# ampli.net
KiCad netlist of a schematic drawn in EAGLE
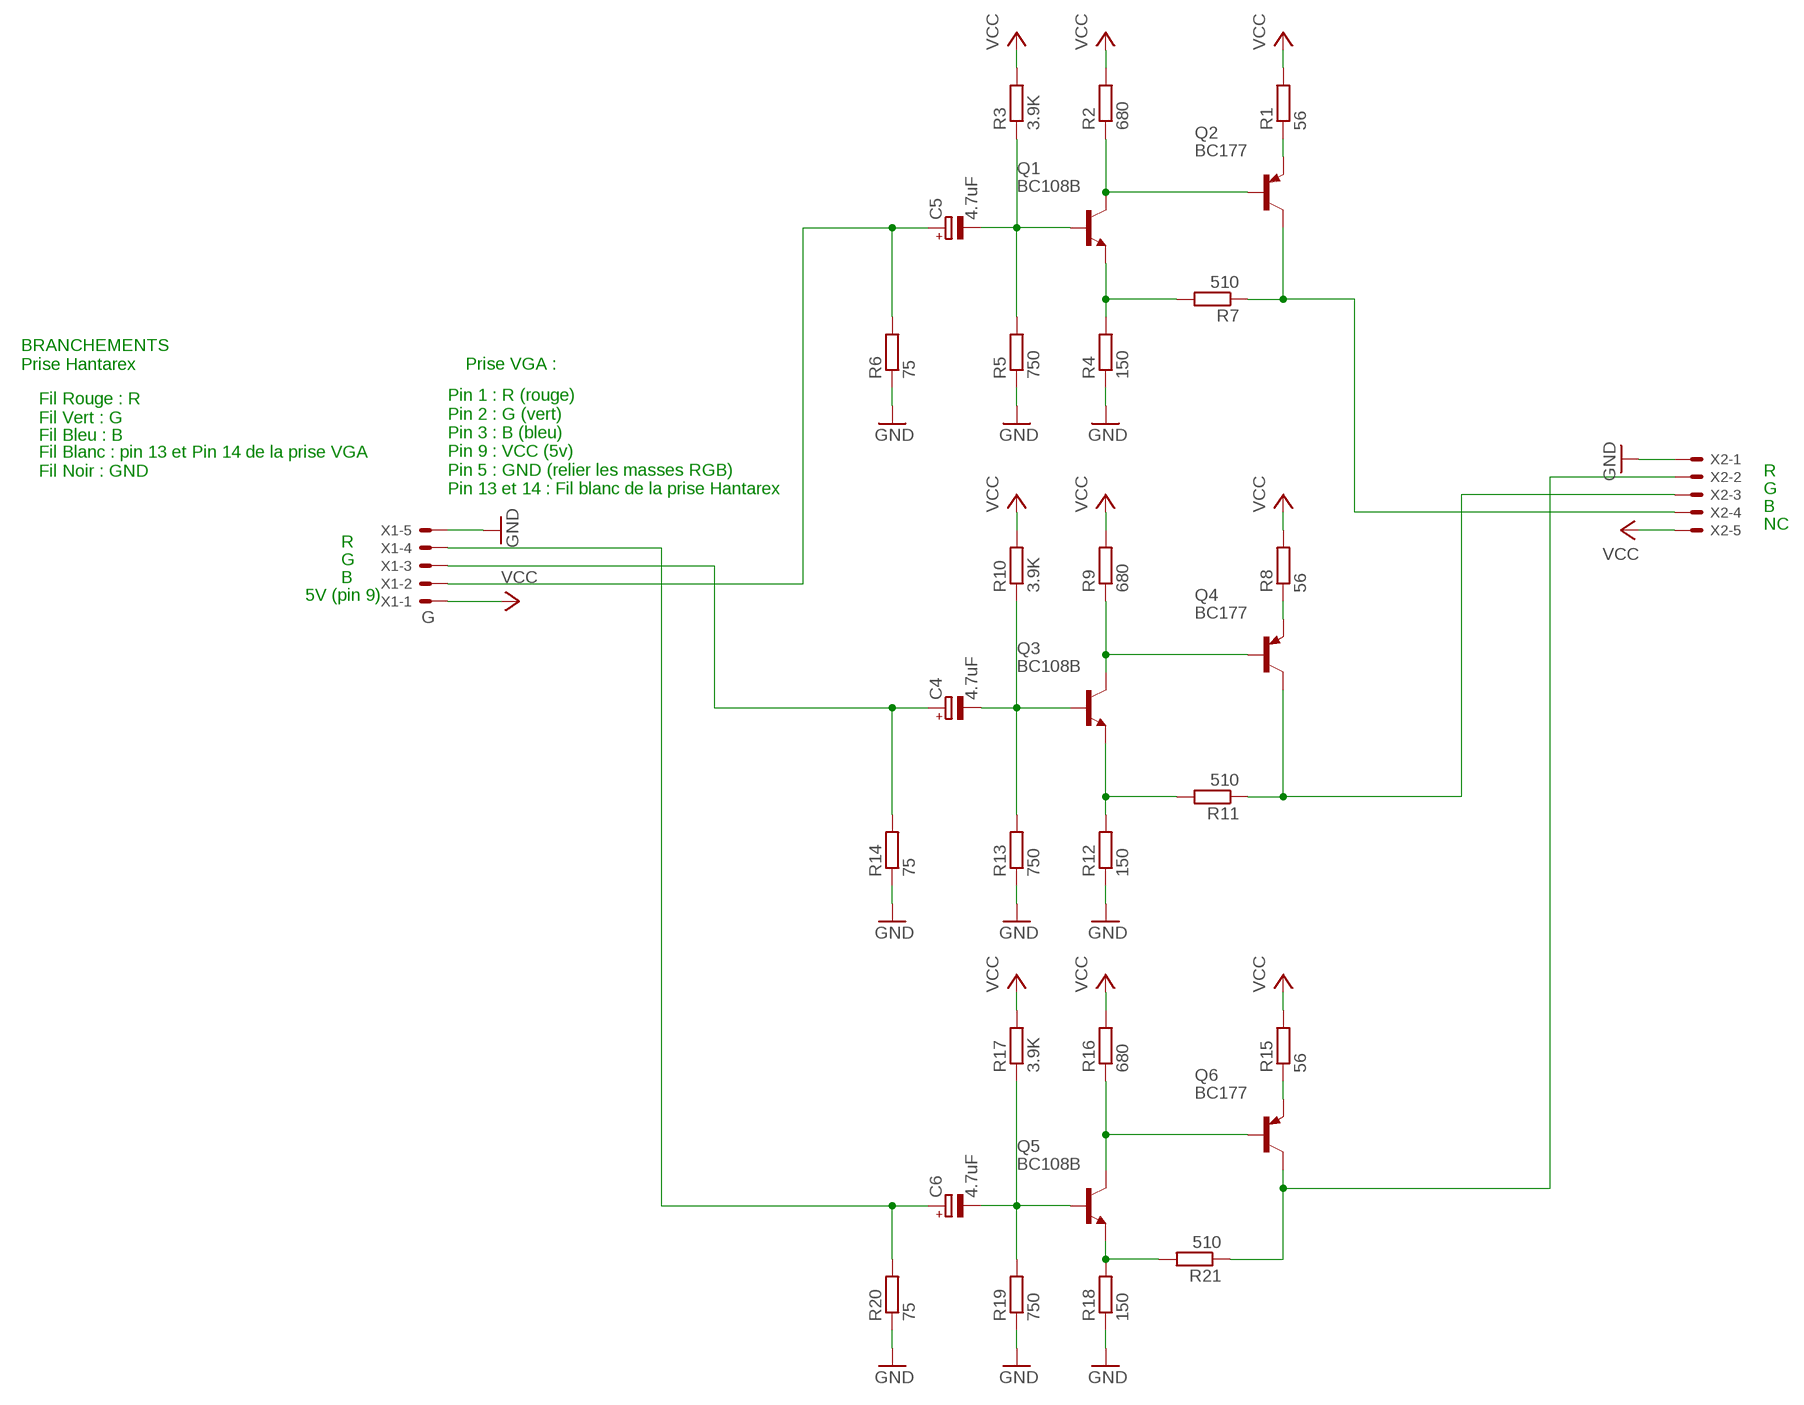
[diagram p0: schematic, sheet 1]

(export (version "E")
  (design (tool "Eeschema 10.0.6"))
  (components
    (comp (ref "C4")
      (value "4.7uF")
      (footprint "eagle-import:E5-10,5")
      (libsource (lib "eagle-import") (part "CPOL-EUE5-10.5"))
    )
    (comp (ref "C5")
      (value "4.7uF")
      (footprint "eagle-import:E5-10,5")
      (libsource (lib "eagle-import") (part "CPOL-EUE5-10.5"))
    )
    (comp (ref "C6")
      (value "4.7uF")
      (footprint "eagle-import:E5-10,5")
      (libsource (lib "eagle-import") (part "CPOL-EUE5-10.5"))
    )
    (comp (ref "Q1")
      (value "BC108B")
      (footprint "eagle-import:TO18")
      (libsource (lib "eagle-import") (part "BC108B"))
    )
    (comp (ref "Q2")
      (value "BC177")
      (footprint "eagle-import:TO18")
      (libsource (lib "eagle-import") (part "BC177"))
    )
    (comp (ref "Q3")
      (value "BC108B")
      (footprint "eagle-import:TO18")
      (libsource (lib "eagle-import") (part "BC108B"))
    )
    (comp (ref "Q4")
      (value "BC177")
      (footprint "eagle-import:TO18")
      (libsource (lib "eagle-import") (part "BC177"))
    )
    (comp (ref "Q5")
      (value "BC108B")
      (footprint "eagle-import:TO18")
      (libsource (lib "eagle-import") (part "BC108B"))
    )
    (comp (ref "Q6")
      (value "BC177")
      (footprint "eagle-import:TO18")
      (libsource (lib "eagle-import") (part "BC177"))
    )
    (comp (ref "R1")
      (value "56")
      (footprint "eagle-import:0207_10")
      (libsource (lib "eagle-import") (part "R-EU_0207/10"))
    )
    (comp (ref "R2")
      (value "680")
      (footprint "eagle-import:0207_10")
      (libsource (lib "eagle-import") (part "R-EU_0207/10"))
    )
    (comp (ref "R3")
      (value "3.9K")
      (footprint "eagle-import:0207_10")
      (libsource (lib "eagle-import") (part "R-EU_0207/10"))
    )
    (comp (ref "R4")
      (value "150")
      (footprint "eagle-import:0207_10")
      (libsource (lib "eagle-import") (part "R-EU_0207/10"))
    )
    (comp (ref "R5")
      (value "750")
      (footprint "eagle-import:0207_10")
      (libsource (lib "eagle-import") (part "R-EU_0207/10"))
    )
    (comp (ref "R6")
      (value "75")
      (footprint "eagle-import:0207_10")
      (libsource (lib "eagle-import") (part "R-EU_0207/10"))
    )
    (comp (ref "R7")
      (value "510")
      (footprint "eagle-import:0207_10")
      (libsource (lib "eagle-import") (part "R-EU_0207/10"))
    )
    (comp (ref "R8")
      (value "56")
      (footprint "eagle-import:0207_10")
      (libsource (lib "eagle-import") (part "R-EU_0207/10"))
    )
    (comp (ref "R9")
      (value "680")
      (footprint "eagle-import:0207_10")
      (libsource (lib "eagle-import") (part "R-EU_0207/10"))
    )
    (comp (ref "R10")
      (value "3.9K")
      (footprint "eagle-import:0207_10")
      (libsource (lib "eagle-import") (part "R-EU_0207/10"))
    )
    (comp (ref "R11")
      (value "510")
      (footprint "eagle-import:0207_10")
      (libsource (lib "eagle-import") (part "R-EU_0207/10"))
    )
    (comp (ref "R12")
      (value "150")
      (footprint "eagle-import:0207_10")
      (libsource (lib "eagle-import") (part "R-EU_0207/10"))
    )
    (comp (ref "R13")
      (value "750")
      (footprint "eagle-import:0207_10")
      (libsource (lib "eagle-import") (part "R-EU_0207/10"))
    )
    (comp (ref "R14")
      (value "75")
      (footprint "eagle-import:0207_10")
      (libsource (lib "eagle-import") (part "R-EU_0207/10"))
    )
    (comp (ref "R15")
      (value "56")
      (footprint "eagle-import:0207_10")
      (libsource (lib "eagle-import") (part "R-EU_0207/10"))
    )
    (comp (ref "R16")
      (value "680")
      (footprint "eagle-import:0207_10")
      (libsource (lib "eagle-import") (part "R-EU_0207/10"))
    )
    (comp (ref "R17")
      (value "3.9K")
      (footprint "eagle-import:0207_10")
      (libsource (lib "eagle-import") (part "R-EU_0207/10"))
    )
    (comp (ref "R18")
      (value "150")
      (footprint "eagle-import:0207_10")
      (libsource (lib "eagle-import") (part "R-EU_0207/10"))
    )
    (comp (ref "R19")
      (value "750")
      (footprint "eagle-import:0207_10")
      (libsource (lib "eagle-import") (part "R-EU_0207/10"))
    )
    (comp (ref "R20")
      (value "75")
      (footprint "eagle-import:0207_10")
      (libsource (lib "eagle-import") (part "R-EU_0207/10"))
    )
    (comp (ref "R21")
      (value "510")
      (footprint "eagle-import:0207_10")
      (libsource (lib "eagle-import") (part "R-EU_0207/10"))
    )
    (comp (ref "X1")
      (value "G")
      (footprint "eagle-import:KK-156-5")
      (libsource (lib "eagle-import") (part "KK-156-5"))
    )
    (comp (ref "X2")
      (value "KK-156-5")
      (footprint "eagle-import:KK-156-5")
      (libsource (lib "eagle-import") (part "KK-156-5"))
    )
  )
  (nets
    (net (code "1") (name "GND") (class "Default")
      (node (ref "R12") (pin "1") (pinfunction "1_1") (pintype "passive"))
      (node (ref "R13") (pin "1") (pinfunction "1_1") (pintype "passive"))
      (node (ref "R14") (pin "1") (pinfunction "1_1") (pintype "passive"))
      (node (ref "R18") (pin "1") (pinfunction "1_1") (pintype "passive"))
      (node (ref "R19") (pin "1") (pinfunction "1_1") (pintype "passive"))
      (node (ref "R20") (pin "1") (pinfunction "1_1") (pintype "passive"))
      (node (ref "R4") (pin "1") (pinfunction "1_1") (pintype "passive"))
      (node (ref "R5") (pin "1") (pinfunction "1_1") (pintype "passive"))
      (node (ref "R6") (pin "1") (pinfunction "1_1") (pintype "passive"))
      (node (ref "X1") (pin "5") (pinfunction "S_5") (pintype "passive"))
      (node (ref "X2") (pin "1") (pinfunction "S_1") (pintype "passive"))
    )
    (net (code "2") (name "Net-(Q1-B)") (class "Default")
      (node (ref "C5") (pin "-") (pinfunction "-_-") (pintype "passive"))
      (node (ref "Q1") (pin "2") (pinfunction "B_2") (pintype "passive"))
      (node (ref "R3") (pin "1") (pinfunction "1_1") (pintype "passive"))
      (node (ref "R5") (pin "2") (pinfunction "2_2") (pintype "passive"))
    )
    (net (code "3") (name "Net-(Q1-C)") (class "Default")
      (node (ref "Q1") (pin "3") (pinfunction "C_3") (pintype "passive"))
      (node (ref "Q2") (pin "2") (pinfunction "B_2") (pintype "passive"))
      (node (ref "R2") (pin "1") (pinfunction "1_1") (pintype "passive"))
    )
    (net (code "4") (name "Net-(Q1-E)") (class "Default")
      (node (ref "Q1") (pin "1") (pinfunction "E_1") (pintype "passive"))
      (node (ref "R4") (pin "2") (pinfunction "2_2") (pintype "passive"))
      (node (ref "R7") (pin "2") (pinfunction "2_2") (pintype "passive"))
    )
    (net (code "5") (name "Net-(Q2-C)") (class "Default")
      (node (ref "Q2") (pin "3") (pinfunction "C_3") (pintype "passive"))
      (node (ref "R7") (pin "1") (pinfunction "1_1") (pintype "passive"))
      (node (ref "X2") (pin "4") (pinfunction "S_4") (pintype "passive"))
    )
    (net (code "6") (name "Net-(Q2-E)") (class "Default")
      (node (ref "Q2") (pin "1") (pinfunction "E_1") (pintype "passive"))
      (node (ref "R1") (pin "1") (pinfunction "1_1") (pintype "passive"))
    )
    (net (code "7") (name "Net-(Q3-B)") (class "Default")
      (node (ref "C4") (pin "-") (pinfunction "-_-") (pintype "passive"))
      (node (ref "Q3") (pin "2") (pinfunction "B_2") (pintype "passive"))
      (node (ref "R10") (pin "1") (pinfunction "1_1") (pintype "passive"))
      (node (ref "R13") (pin "2") (pinfunction "2_2") (pintype "passive"))
    )
    (net (code "8") (name "Net-(Q3-C)") (class "Default")
      (node (ref "Q3") (pin "3") (pinfunction "C_3") (pintype "passive"))
      (node (ref "Q4") (pin "2") (pinfunction "B_2") (pintype "passive"))
      (node (ref "R9") (pin "1") (pinfunction "1_1") (pintype "passive"))
    )
    (net (code "9") (name "Net-(Q3-E)") (class "Default")
      (node (ref "Q3") (pin "1") (pinfunction "E_1") (pintype "passive"))
      (node (ref "R11") (pin "2") (pinfunction "2_2") (pintype "passive"))
      (node (ref "R12") (pin "2") (pinfunction "2_2") (pintype "passive"))
    )
    (net (code "10") (name "Net-(Q4-C)") (class "Default")
      (node (ref "Q4") (pin "3") (pinfunction "C_3") (pintype "passive"))
      (node (ref "R11") (pin "1") (pinfunction "1_1") (pintype "passive"))
      (node (ref "X2") (pin "3") (pinfunction "S_3") (pintype "passive"))
    )
    (net (code "11") (name "Net-(Q4-E)") (class "Default")
      (node (ref "Q4") (pin "1") (pinfunction "E_1") (pintype "passive"))
      (node (ref "R8") (pin "1") (pinfunction "1_1") (pintype "passive"))
    )
    (net (code "12") (name "Net-(Q5-B)") (class "Default")
      (node (ref "C6") (pin "-") (pinfunction "-_-") (pintype "passive"))
      (node (ref "Q5") (pin "2") (pinfunction "B_2") (pintype "passive"))
      (node (ref "R17") (pin "1") (pinfunction "1_1") (pintype "passive"))
      (node (ref "R19") (pin "2") (pinfunction "2_2") (pintype "passive"))
    )
    (net (code "13") (name "Net-(Q5-C)") (class "Default")
      (node (ref "Q5") (pin "3") (pinfunction "C_3") (pintype "passive"))
      (node (ref "Q6") (pin "2") (pinfunction "B_2") (pintype "passive"))
      (node (ref "R16") (pin "1") (pinfunction "1_1") (pintype "passive"))
    )
    (net (code "14") (name "Net-(Q5-E)") (class "Default")
      (node (ref "Q5") (pin "1") (pinfunction "E_1") (pintype "passive"))
      (node (ref "R18") (pin "2") (pinfunction "2_2") (pintype "passive"))
      (node (ref "R21") (pin "2") (pinfunction "2_2") (pintype "passive"))
    )
    (net (code "15") (name "Net-(Q6-C)") (class "Default")
      (node (ref "Q6") (pin "3") (pinfunction "C_3") (pintype "passive"))
      (node (ref "R21") (pin "1") (pinfunction "1_1") (pintype "passive"))
      (node (ref "X2") (pin "2") (pinfunction "S_2") (pintype "passive"))
    )
    (net (code "16") (name "Net-(Q6-E)") (class "Default")
      (node (ref "Q6") (pin "1") (pinfunction "E_1") (pintype "passive"))
      (node (ref "R15") (pin "1") (pinfunction "1_1") (pintype "passive"))
    )
    (net (code "17") (name "Net-(X1B-S)") (class "Default")
      (node (ref "C5") (pin "+") (pinfunction "+_+") (pintype "passive"))
      (node (ref "R6") (pin "2") (pinfunction "2_2") (pintype "passive"))
      (node (ref "X1") (pin "2") (pinfunction "S_2") (pintype "passive"))
    )
    (net (code "18") (name "Net-(X1C-S)") (class "Default")
      (node (ref "C4") (pin "+") (pinfunction "+_+") (pintype "passive"))
      (node (ref "R14") (pin "2") (pinfunction "2_2") (pintype "passive"))
      (node (ref "X1") (pin "3") (pinfunction "S_3") (pintype "passive"))
    )
    (net (code "19") (name "Net-(X1D-S)") (class "Default")
      (node (ref "C6") (pin "+") (pinfunction "+_+") (pintype "passive"))
      (node (ref "R20") (pin "2") (pinfunction "2_2") (pintype "passive"))
      (node (ref "X1") (pin "4") (pinfunction "S_4") (pintype "passive"))
    )
    (net (code "20") (name "VCC") (class "Default")
      (node (ref "R1") (pin "2") (pinfunction "2_2") (pintype "passive"))
      (node (ref "R10") (pin "2") (pinfunction "2_2") (pintype "passive"))
      (node (ref "R15") (pin "2") (pinfunction "2_2") (pintype "passive"))
      (node (ref "R16") (pin "2") (pinfunction "2_2") (pintype "passive"))
      (node (ref "R17") (pin "2") (pinfunction "2_2") (pintype "passive"))
      (node (ref "R2") (pin "2") (pinfunction "2_2") (pintype "passive"))
      (node (ref "R3") (pin "2") (pinfunction "2_2") (pintype "passive"))
      (node (ref "R8") (pin "2") (pinfunction "2_2") (pintype "passive"))
      (node (ref "R9") (pin "2") (pinfunction "2_2") (pintype "passive"))
      (node (ref "X1") (pin "1") (pinfunction "S_1") (pintype "passive"))
      (node (ref "X2") (pin "5") (pinfunction "S_5") (pintype "passive"))
    )
  )
)
